# Eliz.net
KiCad netlist of a schematic drawn in EAGLE
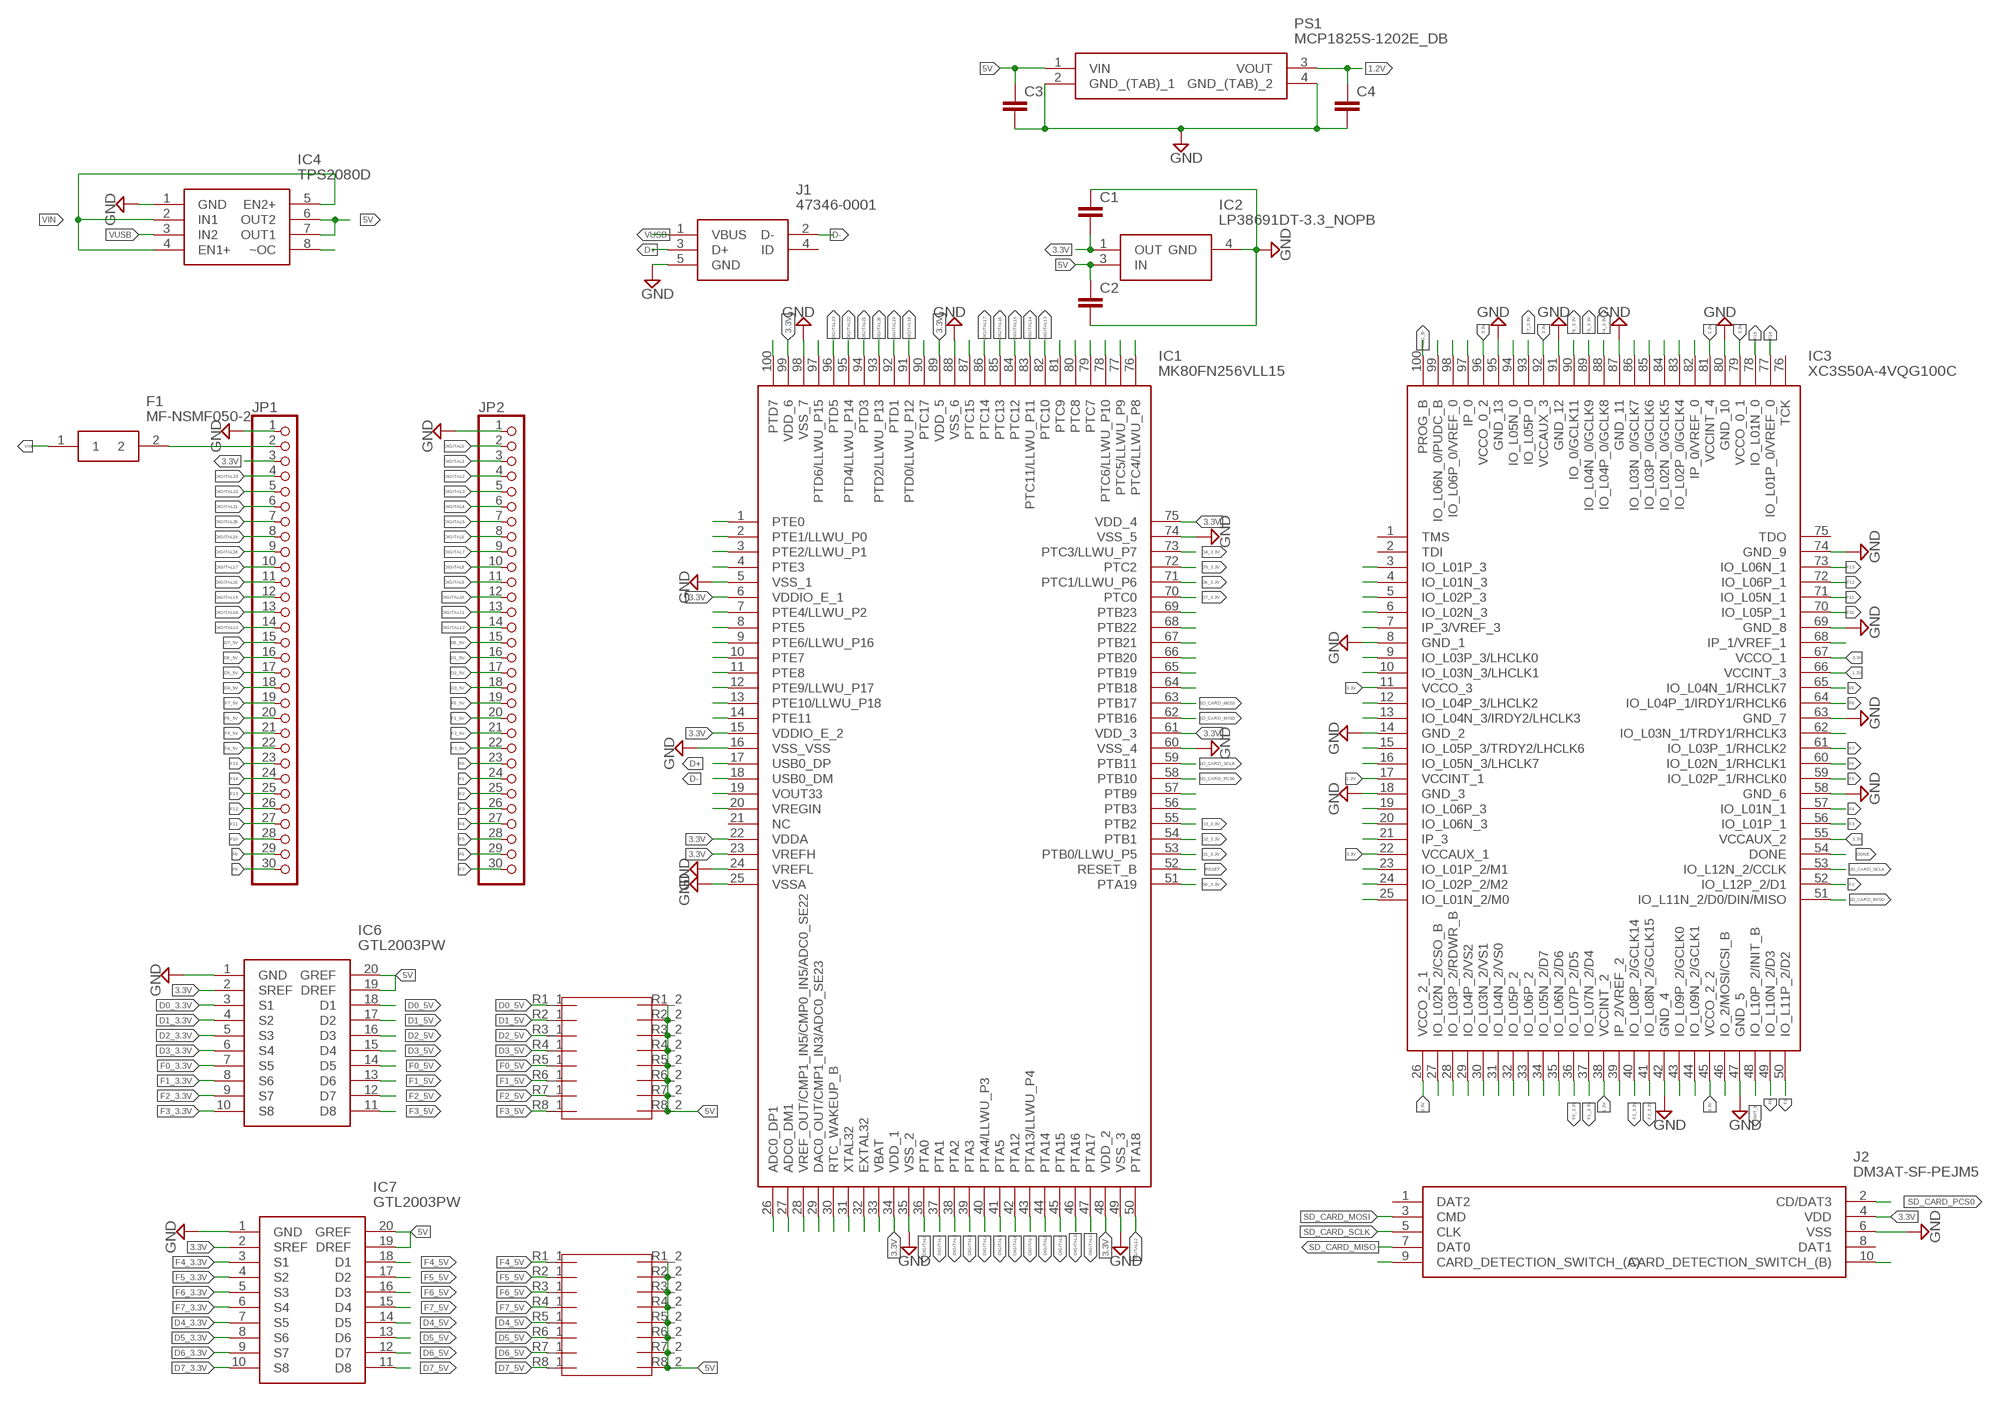
[diagram p0: schematic, sheet 1]

(export (version "E")
  (design (tool "Eeschema 10.0.6"))
  (components
    (comp (ref "C1")
      (value "C-EUC0805")
      (footprint "eagle-import:C0805")
      (libsource (lib "eagle-import") (part "C-EUC0805"))
    )
    (comp (ref "C2")
      (value "C-EUC0805")
      (footprint "eagle-import:C0805")
      (libsource (lib "eagle-import") (part "C-EUC0805"))
    )
    (comp (ref "C3")
      (value "C-EUC0805")
      (footprint "eagle-import:C0805")
      (libsource (lib "eagle-import") (part "C-EUC0805"))
    )
    (comp (ref "C4")
      (value "C-EUC0805")
      (footprint "eagle-import:C0805")
      (libsource (lib "eagle-import") (part "C-EUC0805"))
    )
    (comp (ref "F1")
      (value "MF-NSMF050-2")
      (footprint "eagle-import:FUSC3216X85N")
      (fields (field (name "RS_PART_NUMBER") "6478320P"))
      (libsource (lib "eagle-import") (part "MF-NSMF050-2"))
    )
    (comp (ref "IC1")
      (value "MK80FN256VLL15")
      (footprint "eagle-import:QFP50P1600X1600X170-100N")
      (libsource (lib "eagle-import") (part "MK80FN256VLL15"))
    )
    (comp (ref "IC2")
      (value "LP38691DT-3.3_NOPB")
      (footprint "eagle-import:TO228P991X238-3N")
      (fields
        (field (name "ARROW_PART_NUMBER") "LP38691DT-3.3/NOPB")
        (field (name "RS_PART_NUMBER") "5378730P")
      )
      (libsource (lib "eagle-import") (part "LP38691DT-3.3_NOPB"))
    )
    (comp (ref "IC3")
      (value "XC3S50A-4VQG100C")
      (footprint "eagle-import:QFP50P1600X1600X120-100N")
      (fields (field (name "RS_PART_NUMBER") "1732062"))
      (libsource (lib "eagle-import") (part "XC3S50A-4VQG100C"))
    )
    (comp (ref "IC4")
      (value "TPS2080D")
      (footprint "eagle-import:SOIC127P600X175-8N")
      (fields (field (name "RS_PART_NUMBER") "6608007P"))
      (libsource (lib "eagle-import") (part "TPS2080D"))
    )
    (comp (ref "IC6")
      (value "GTL2003PW")
      (footprint "eagle-import:SOP65P640X110-20N")
      (fields (field (name "RS_PART_NUMBER") "510960"))
      (libsource (lib "eagle-import") (part "GTL2003PW"))
    )
    (comp (ref "IC7")
      (value "GTL2003PW")
      (footprint "eagle-import:SOP65P640X110-20N")
      (fields (field (name "RS_PART_NUMBER") "510960"))
      (libsource (lib "eagle-import") (part "GTL2003PW"))
    )
    (comp (ref "J1")
      (value "47346-0001")
      (footprint "eagle-import:47346-0001")
      (fields (field (name "RS_PART_NUMBER") "7025475P"))
      (libsource (lib "eagle-import") (part "47346-0001"))
    )
    (comp (ref "J2")
      (value "DM3AT-SF-PEJM5")
      (footprint "eagle-import:DM3AT-SF-PEJM5_1")
      (fields (field (name "RS_PART_NUMBER") "1722520"))
      (libsource (lib "eagle-import") (part "DM3AT-SF-PEJM5"))
    )
    (comp (ref "JP1")
      (value "PINHD-1X30")
      (footprint "eagle-import:1X30")
      (libsource (lib "eagle-import") (part "PINHD-1X30"))
    )
    (comp (ref "JP2")
      (value "PINHD-1X30")
      (footprint "eagle-import:1X30")
      (libsource (lib "eagle-import") (part "PINHD-1X30"))
    )
    (comp (ref "PS1")
      (value "MCP1825S-1202E_DB")
      (footprint "eagle-import:SOT230P700X180-4N")
      (fields
        (field (name "ARROW_PART_NUMBER") "MCP1825S-1202E/DB")
        (field (name "RS_PART_NUMBER") "1651983")
      )
      (libsource (lib "eagle-import") (part "MCP1825S-1202E_DB"))
    )
    (comp (ref "U$1")
      (value "EXB2HV472JV")
      (footprint "eagle-import:8_4,7KOHM")
      (fields (field (name "MF") "Panasonic"))
      (libsource (lib "eagle-import") (part "EXB2HV472JV"))
    )
    (comp (ref "U$2")
      (value "EXB2HV472JV")
      (footprint "eagle-import:8_4,7KOHM")
      (fields (field (name "MF") "Panasonic"))
      (libsource (lib "eagle-import") (part "EXB2HV472JV"))
    )
  )
  (nets
    (net (code "1") (name "1.2V") (class "Default")
      (node (ref "C4") (pin "1") (pinfunction "1_1") (pintype "passive"))
      (node (ref "IC3") (pin "17") (pinfunction "VCCINT_1_17") (pintype "bidirectional"))
      (node (ref "IC3") (pin "38") (pinfunction "VCCINT_2_38") (pintype "bidirectional"))
      (node (ref "IC3") (pin "66") (pinfunction "VCCINT_3_66") (pintype "bidirectional"))
      (node (ref "IC3") (pin "81") (pinfunction "VCCINT_4_81") (pintype "bidirectional"))
      (node (ref "PS1") (pin "3") (pinfunction "VOUT_3") (pintype "output"))
    )
    (net (code "2") (name "3.3V") (class "Default")
      (node (ref "C1") (pin "2") (pinfunction "2_2") (pintype "passive"))
      (node (ref "IC1") (pin "15") (pinfunction "VDDIO_E_2_15") (pintype "bidirectional"))
      (node (ref "IC1") (pin "22") (pinfunction "VDDA_22") (pintype "bidirectional"))
      (node (ref "IC1") (pin "23") (pinfunction "VREFH_23") (pintype "bidirectional"))
      (node (ref "IC1") (pin "34") (pinfunction "VDD_1_34") (pintype "bidirectional"))
      (node (ref "IC1") (pin "48") (pinfunction "VDD_2_48") (pintype "bidirectional"))
      (node (ref "IC1") (pin "6") (pinfunction "VDDIO_E_1_6") (pintype "bidirectional"))
      (node (ref "IC1") (pin "61") (pinfunction "VDD_3_61") (pintype "bidirectional"))
      (node (ref "IC1") (pin "75") (pinfunction "VDD_4_75") (pintype "bidirectional"))
      (node (ref "IC1") (pin "89") (pinfunction "VDD_5_89") (pintype "bidirectional"))
      (node (ref "IC1") (pin "99") (pinfunction "VDD_6_99") (pintype "bidirectional"))
      (node (ref "IC2") (pin "1") (pinfunction "OUT_1") (pintype "output"))
      (node (ref "IC3") (pin "11") (pinfunction "VCCO_3_11") (pintype "bidirectional"))
      (node (ref "IC3") (pin "22") (pinfunction "VCCAUX_1_22") (pintype "bidirectional"))
      (node (ref "IC3") (pin "26") (pinfunction "VCCO_2_1_26") (pintype "bidirectional"))
      (node (ref "IC3") (pin "45") (pinfunction "VCCO_2_2_45") (pintype "bidirectional"))
      (node (ref "IC3") (pin "55") (pinfunction "VCCAUX_2_55") (pintype "bidirectional"))
      (node (ref "IC3") (pin "67") (pinfunction "VCCO_1_67") (pintype "bidirectional"))
      (node (ref "IC3") (pin "79") (pinfunction "VCCO_0_1_79") (pintype "bidirectional"))
      (node (ref "IC3") (pin "92") (pinfunction "VCCAUX_3_92") (pintype "bidirectional"))
      (node (ref "IC3") (pin "96") (pinfunction "VCCO_0_2_96") (pintype "bidirectional"))
      (node (ref "IC6") (pin "2") (pinfunction "SREF_2") (pintype "input"))
      (node (ref "IC7") (pin "2") (pinfunction "SREF_2") (pintype "input"))
      (node (ref "J2") (pin "4") (pinfunction "VDD_4") (pintype "bidirectional"))
      (node (ref "JP1") (pin "3") (pinfunction "3_3") (pintype "passive"))
    )
    (net (code "3") (name "5V") (class "Default")
      (node (ref "C2") (pin "1") (pinfunction "1_1") (pintype "passive"))
      (node (ref "C3") (pin "1") (pinfunction "1_1") (pintype "passive"))
      (node (ref "IC2") (pin "3") (pinfunction "IN_3") (pintype "input"))
      (node (ref "IC4") (pin "6") (pinfunction "OUT2_6") (pintype "bidirectional"))
      (node (ref "IC4") (pin "7") (pinfunction "OUT1_7") (pintype "bidirectional"))
      (node (ref "IC6") (pin "19") (pinfunction "DREF_19") (pintype "input"))
      (node (ref "IC6") (pin "20") (pinfunction "GREF_20") (pintype "input"))
      (node (ref "IC7") (pin "19") (pinfunction "DREF_19") (pintype "input"))
      (node (ref "IC7") (pin "20") (pinfunction "GREF_20") (pintype "input"))
      (node (ref "PS1") (pin "1") (pinfunction "VIN_1") (pintype "input"))
      (node (ref "U$1") (pin "R1_2") (pinfunction "R1_2_R1_2") (pintype "bidirectional"))
      (node (ref "U$1") (pin "R2_2") (pinfunction "R2_2_R2_2") (pintype "bidirectional"))
      (node (ref "U$1") (pin "R3_2") (pinfunction "R3_2_R3_2") (pintype "bidirectional"))
      (node (ref "U$1") (pin "R4_2") (pinfunction "R4_2_R4_2") (pintype "bidirectional"))
      (node (ref "U$1") (pin "R5_2") (pinfunction "R5_2_R5_2") (pintype "bidirectional"))
      (node (ref "U$1") (pin "R6_2") (pinfunction "R6_2_R6_2") (pintype "bidirectional"))
      (node (ref "U$1") (pin "R7_2") (pinfunction "R7_2_R7_2") (pintype "bidirectional"))
      (node (ref "U$1") (pin "R8_2") (pinfunction "R8_2_R8_2") (pintype "bidirectional"))
      (node (ref "U$2") (pin "R1_2") (pinfunction "R1_2_R1_2") (pintype "bidirectional"))
      (node (ref "U$2") (pin "R2_2") (pinfunction "R2_2_R2_2") (pintype "bidirectional"))
      (node (ref "U$2") (pin "R3_2") (pinfunction "R3_2_R3_2") (pintype "bidirectional"))
      (node (ref "U$2") (pin "R4_2") (pinfunction "R4_2_R4_2") (pintype "bidirectional"))
      (node (ref "U$2") (pin "R5_2") (pinfunction "R5_2_R5_2") (pintype "bidirectional"))
      (node (ref "U$2") (pin "R6_2") (pinfunction "R6_2_R6_2") (pintype "bidirectional"))
      (node (ref "U$2") (pin "R7_2") (pinfunction "R7_2_R7_2") (pintype "bidirectional"))
      (node (ref "U$2") (pin "R8_2") (pinfunction "R8_2_R8_2") (pintype "bidirectional"))
    )
    (net (code "4") (name "D+") (class "Default")
      (node (ref "IC1") (pin "17") (pinfunction "USB0_DP_17") (pintype "bidirectional"))
      (node (ref "J1") (pin "3") (pinfunction "D+_3") (pintype "bidirectional"))
    )
    (net (code "5") (name "D-") (class "Default")
      (node (ref "IC1") (pin "18") (pinfunction "USB0_DM_18") (pintype "bidirectional"))
      (node (ref "J1") (pin "2") (pinfunction "D-_2") (pintype "bidirectional"))
    )
    (net (code "6") (name "D0_3.3V") (class "Default")
      (node (ref "IC1") (pin "51") (pinfunction "PTA19_51") (pintype "bidirectional"))
      (node (ref "IC6") (pin "3") (pinfunction "S1_3") (pintype "bidirectional"))
    )
    (net (code "7") (name "D0_5V") (class "Default")
      (node (ref "IC6") (pin "18") (pinfunction "D1_18") (pintype "bidirectional"))
      (node (ref "JP2") (pin "15") (pinfunction "15_15") (pintype "passive"))
      (node (ref "U$1") (pin "R1_1") (pinfunction "R1_1_R1_1") (pintype "bidirectional"))
    )
    (net (code "8") (name "D1_3.3V") (class "Default")
      (node (ref "IC1") (pin "53") (pinfunction "PTB0/LLWU_P5_53") (pintype "bidirectional"))
      (node (ref "IC6") (pin "4") (pinfunction "S2_4") (pintype "bidirectional"))
    )
    (net (code "9") (name "D1_5V") (class "Default")
      (node (ref "IC6") (pin "17") (pinfunction "D2_17") (pintype "bidirectional"))
      (node (ref "JP2") (pin "16") (pinfunction "16_16") (pintype "passive"))
      (node (ref "U$1") (pin "R2_1") (pinfunction "R2_1_R2_1") (pintype "bidirectional"))
    )
    (net (code "10") (name "D2_3.3V") (class "Default")
      (node (ref "IC1") (pin "54") (pinfunction "PTB1_54") (pintype "bidirectional"))
      (node (ref "IC6") (pin "5") (pinfunction "S3_5") (pintype "bidirectional"))
    )
    (net (code "11") (name "D2_5V") (class "Default")
      (node (ref "IC6") (pin "16") (pinfunction "D3_16") (pintype "bidirectional"))
      (node (ref "JP2") (pin "17") (pinfunction "17_17") (pintype "passive"))
      (node (ref "U$1") (pin "R3_1") (pinfunction "R3_1_R3_1") (pintype "bidirectional"))
    )
    (net (code "12") (name "D3_3.3V") (class "Default")
      (node (ref "IC1") (pin "55") (pinfunction "PTB2_55") (pintype "bidirectional"))
      (node (ref "IC6") (pin "6") (pinfunction "S4_6") (pintype "bidirectional"))
    )
    (net (code "13") (name "D3_5V") (class "Default")
      (node (ref "IC6") (pin "15") (pinfunction "D4_15") (pintype "bidirectional"))
      (node (ref "JP2") (pin "18") (pinfunction "18_18") (pintype "passive"))
      (node (ref "U$1") (pin "R4_1") (pinfunction "R4_1_R4_1") (pintype "bidirectional"))
    )
    (net (code "14") (name "D4_3.3V") (class "Default")
      (node (ref "IC1") (pin "73") (pinfunction "PTC3/LLWU_P7_73") (pintype "bidirectional"))
      (node (ref "IC7") (pin "7") (pinfunction "S5_7") (pintype "bidirectional"))
    )
    (net (code "15") (name "D4_5V") (class "Default")
      (node (ref "IC7") (pin "14") (pinfunction "D5_14") (pintype "bidirectional"))
      (node (ref "JP1") (pin "18") (pinfunction "18_18") (pintype "passive"))
      (node (ref "U$2") (pin "R5_1") (pinfunction "R5_1_R5_1") (pintype "bidirectional"))
    )
    (net (code "16") (name "D5_3.3V") (class "Default")
      (node (ref "IC1") (pin "72") (pinfunction "PTC2_72") (pintype "bidirectional"))
      (node (ref "IC7") (pin "8") (pinfunction "S6_8") (pintype "bidirectional"))
    )
    (net (code "17") (name "D5_5V") (class "Default")
      (node (ref "IC7") (pin "13") (pinfunction "D6_13") (pintype "bidirectional"))
      (node (ref "JP1") (pin "17") (pinfunction "17_17") (pintype "passive"))
      (node (ref "U$2") (pin "R6_1") (pinfunction "R6_1_R6_1") (pintype "bidirectional"))
    )
    (net (code "18") (name "D6_3.3V") (class "Default")
      (node (ref "IC1") (pin "71") (pinfunction "PTC1/LLWU_P6_71") (pintype "bidirectional"))
      (node (ref "IC7") (pin "9") (pinfunction "S7_9") (pintype "bidirectional"))
    )
    (net (code "19") (name "D6_5V") (class "Default")
      (node (ref "IC7") (pin "12") (pinfunction "D7_12") (pintype "bidirectional"))
      (node (ref "JP1") (pin "16") (pinfunction "16_16") (pintype "passive"))
      (node (ref "U$2") (pin "R7_1") (pinfunction "R7_1_R7_1") (pintype "bidirectional"))
    )
    (net (code "20") (name "D7_3.3V") (class "Default")
      (node (ref "IC1") (pin "70") (pinfunction "PTC0_70") (pintype "bidirectional"))
      (node (ref "IC7") (pin "10") (pinfunction "S8_10") (pintype "bidirectional"))
    )
    (net (code "21") (name "D7_5V") (class "Default")
      (node (ref "IC7") (pin "11") (pinfunction "D8_11") (pintype "bidirectional"))
      (node (ref "JP1") (pin "15") (pinfunction "15_15") (pintype "passive"))
      (node (ref "U$2") (pin "R8_1") (pinfunction "R8_1_R8_1") (pintype "bidirectional"))
    )
    (net (code "22") (name "DIGITAL0") (class "Default")
      (node (ref "IC1") (pin "36") (pinfunction "PTA0_36") (pintype "bidirectional"))
      (node (ref "JP2") (pin "2") (pinfunction "2_2") (pintype "passive"))
    )
    (net (code "23") (name "DIGITAL1") (class "Default")
      (node (ref "IC1") (pin "37") (pinfunction "PTA1_37") (pintype "bidirectional"))
      (node (ref "JP2") (pin "3") (pinfunction "3_3") (pintype "passive"))
    )
    (net (code "24") (name "DIGITAL2") (class "Default")
      (node (ref "IC1") (pin "38") (pinfunction "PTA2_38") (pintype "bidirectional"))
      (node (ref "JP2") (pin "4") (pinfunction "4_4") (pintype "passive"))
    )
    (net (code "25") (name "DIGITAL3") (class "Default")
      (node (ref "IC1") (pin "39") (pinfunction "PTA3_39") (pintype "bidirectional"))
      (node (ref "JP2") (pin "5") (pinfunction "5_5") (pintype "passive"))
    )
    (net (code "26") (name "DIGITAL4") (class "Default")
      (node (ref "IC1") (pin "40") (pinfunction "PTA4/LLWU_P3_40") (pintype "bidirectional"))
      (node (ref "JP2") (pin "6") (pinfunction "6_6") (pintype "passive"))
    )
    (net (code "27") (name "DIGITAL5") (class "Default")
      (node (ref "IC1") (pin "41") (pinfunction "PTA5_41") (pintype "bidirectional"))
      (node (ref "JP2") (pin "7") (pinfunction "7_7") (pintype "passive"))
    )
    (net (code "28") (name "DIGITAL6") (class "Default")
      (node (ref "IC1") (pin "42") (pinfunction "PTA12_42") (pintype "bidirectional"))
      (node (ref "JP2") (pin "8") (pinfunction "8_8") (pintype "passive"))
    )
    (net (code "29") (name "DIGITAL7") (class "Default")
      (node (ref "IC1") (pin "43") (pinfunction "PTA13/LLWU_P4_43") (pintype "bidirectional"))
      (node (ref "JP2") (pin "9") (pinfunction "9_9") (pintype "passive"))
    )
    (net (code "30") (name "DIGITAL8") (class "Default")
      (node (ref "IC1") (pin "44") (pinfunction "PTA14_44") (pintype "bidirectional"))
      (node (ref "JP2") (pin "10") (pinfunction "10_10") (pintype "passive"))
    )
    (net (code "31") (name "DIGITAL9") (class "Default")
      (node (ref "IC1") (pin "45") (pinfunction "PTA15_45") (pintype "bidirectional"))
      (node (ref "JP2") (pin "11") (pinfunction "11_11") (pintype "passive"))
    )
    (net (code "32") (name "DIGITAL10") (class "Default")
      (node (ref "IC1") (pin "46") (pinfunction "PTA16_46") (pintype "bidirectional"))
      (node (ref "JP2") (pin "12") (pinfunction "12_12") (pintype "passive"))
    )
    (net (code "33") (name "DIGITAL11") (class "Default")
      (node (ref "IC1") (pin "47") (pinfunction "PTA17_47") (pintype "bidirectional"))
      (node (ref "JP2") (pin "13") (pinfunction "13_13") (pintype "passive"))
    )
    (net (code "34") (name "DIGITAL12") (class "Default")
      (node (ref "IC1") (pin "50") (pinfunction "PTA18_50") (pintype "bidirectional"))
      (node (ref "JP2") (pin "14") (pinfunction "14_14") (pintype "passive"))
    )
    (net (code "35") (name "DIGITAL13") (class "Default")
      (node (ref "IC1") (pin "82") (pinfunction "PTC10_82") (pintype "bidirectional"))
      (node (ref "JP1") (pin "14") (pinfunction "14_14") (pintype "passive"))
    )
    (net (code "36") (name "DIGITAL14") (class "Default")
      (node (ref "IC1") (pin "83") (pinfunction "PTC11/LLWU_P11_83") (pintype "bidirectional"))
      (node (ref "JP1") (pin "13") (pinfunction "13_13") (pintype "passive"))
    )
    (net (code "37") (name "DIGITAL15") (class "Default")
      (node (ref "IC1") (pin "84") (pinfunction "PTC12_84") (pintype "bidirectional"))
      (node (ref "JP1") (pin "12") (pinfunction "12_12") (pintype "passive"))
    )
    (net (code "38") (name "DIGITAL16") (class "Default")
      (node (ref "IC1") (pin "85") (pinfunction "PTC13_85") (pintype "bidirectional"))
      (node (ref "JP1") (pin "11") (pinfunction "11_11") (pintype "passive"))
    )
    (net (code "39") (name "DIGITAL17") (class "Default")
      (node (ref "IC1") (pin "86") (pinfunction "PTC14_86") (pintype "bidirectional"))
      (node (ref "JP1") (pin "10") (pinfunction "10_10") (pintype "passive"))
    )
    (net (code "40") (name "DIGITAL18") (class "Default")
      (node (ref "IC1") (pin "91") (pinfunction "PTD0/LLWU_P12_91") (pintype "bidirectional"))
      (node (ref "JP1") (pin "9") (pinfunction "9_9") (pintype "passive"))
    )
    (net (code "41") (name "DIGITAL19") (class "Default")
      (node (ref "IC1") (pin "92") (pinfunction "PTD1_92") (pintype "bidirectional"))
      (node (ref "JP1") (pin "8") (pinfunction "8_8") (pintype "passive"))
    )
    (net (code "42") (name "DIGITAL20") (class "Default")
      (node (ref "IC1") (pin "93") (pinfunction "PTD2/LLWU_P13_93") (pintype "bidirectional"))
      (node (ref "JP1") (pin "7") (pinfunction "7_7") (pintype "passive"))
    )
    (net (code "43") (name "DIGITAL21") (class "Default")
      (node (ref "IC1") (pin "94") (pinfunction "PTD3_94") (pintype "bidirectional"))
      (node (ref "JP1") (pin "6") (pinfunction "6_6") (pintype "passive"))
    )
    (net (code "44") (name "DIGITAL22") (class "Default")
      (node (ref "IC1") (pin "95") (pinfunction "PTD4/LLWU_P14_95") (pintype "bidirectional"))
      (node (ref "JP1") (pin "5") (pinfunction "5_5") (pintype "passive"))
    )
    (net (code "45") (name "DIGITAL23") (class "Default")
      (node (ref "IC1") (pin "96") (pinfunction "PTD5_96") (pintype "bidirectional"))
      (node (ref "JP1") (pin "4") (pinfunction "4_4") (pintype "passive"))
    )
    (net (code "46") (name "DONE") (class "Default")
      (node (ref "IC3") (pin "54") (pinfunction "DONE_54") (pintype "bidirectional"))
    )
    (net (code "47") (name "F0") (class "Default")
      (node (ref "IC3") (pin "49") (pinfunction "IO_L10N_2/D3_49") (pintype "bidirectional"))
      (node (ref "JP2") (pin "23") (pinfunction "23_23") (pintype "passive"))
    )
    (net (code "48") (name "F0_3.3V") (class "Default")
      (node (ref "IC3") (pin "36") (pinfunction "IO_L07P_2/D5_36") (pintype "bidirectional"))
      (node (ref "IC6") (pin "7") (pinfunction "S5_7") (pintype "bidirectional"))
    )
    (net (code "49") (name "F0_5V") (class "Default")
      (node (ref "IC6") (pin "14") (pinfunction "D5_14") (pintype "bidirectional"))
      (node (ref "JP2") (pin "19") (pinfunction "19_19") (pintype "passive"))
      (node (ref "U$1") (pin "R5_1") (pinfunction "R5_1_R5_1") (pintype "bidirectional"))
    )
    (net (code "50") (name "F1") (class "Default")
      (node (ref "IC3") (pin "50") (pinfunction "IO_L11P_2/D2_50") (pintype "bidirectional"))
      (node (ref "JP2") (pin "24") (pinfunction "24_24") (pintype "passive"))
    )
    (net (code "51") (name "F1_3.3V") (class "Default")
      (node (ref "IC3") (pin "37") (pinfunction "IO_L07N_2/D4_37") (pintype "bidirectional"))
      (node (ref "IC6") (pin "8") (pinfunction "S6_8") (pintype "bidirectional"))
    )
    (net (code "52") (name "F1_5V") (class "Default")
      (node (ref "IC6") (pin "13") (pinfunction "D6_13") (pintype "bidirectional"))
      (node (ref "JP2") (pin "20") (pinfunction "20_20") (pintype "passive"))
      (node (ref "U$1") (pin "R6_1") (pinfunction "R6_1_R6_1") (pintype "bidirectional"))
    )
    (net (code "53") (name "F2") (class "Default")
      (node (ref "IC3") (pin "52") (pinfunction "IO_L12P_2/D1_52") (pintype "bidirectional"))
      (node (ref "JP2") (pin "25") (pinfunction "25_25") (pintype "passive"))
    )
    (net (code "54") (name "F2_3.3V") (class "Default")
      (node (ref "IC3") (pin "40") (pinfunction "IO_L08P_2/GCLK14_40") (pintype "bidirectional"))
      (node (ref "IC6") (pin "9") (pinfunction "S7_9") (pintype "bidirectional"))
    )
    (net (code "55") (name "F2_5V") (class "Default")
      (node (ref "IC6") (pin "12") (pinfunction "D7_12") (pintype "bidirectional"))
      (node (ref "JP2") (pin "21") (pinfunction "21_21") (pintype "passive"))
      (node (ref "U$1") (pin "R7_1") (pinfunction "R7_1_R7_1") (pintype "bidirectional"))
    )
    (net (code "56") (name "F3") (class "Default")
      (node (ref "IC3") (pin "56") (pinfunction "IO_L01P_1_56") (pintype "bidirectional"))
      (node (ref "JP2") (pin "26") (pinfunction "26_26") (pintype "passive"))
    )
    (net (code "57") (name "F3_3.3V") (class "Default")
      (node (ref "IC3") (pin "41") (pinfunction "IO_L08N_2/GCLK15_41") (pintype "bidirectional"))
      (node (ref "IC6") (pin "10") (pinfunction "S8_10") (pintype "bidirectional"))
    )
    (net (code "58") (name "F3_5V") (class "Default")
      (node (ref "IC6") (pin "11") (pinfunction "D8_11") (pintype "bidirectional"))
      (node (ref "JP2") (pin "22") (pinfunction "22_22") (pintype "passive"))
      (node (ref "U$1") (pin "R8_1") (pinfunction "R8_1_R8_1") (pintype "bidirectional"))
    )
    (net (code "59") (name "F4") (class "Default")
      (node (ref "IC3") (pin "57") (pinfunction "IO_L01N_1_57") (pintype "bidirectional"))
      (node (ref "JP2") (pin "27") (pinfunction "27_27") (pintype "passive"))
    )
    (net (code "60") (name "F4_3.3V") (class "Default")
      (node (ref "IC3") (pin "88") (pinfunction "IO_L04P_0/GCLK8_88") (pintype "bidirectional"))
      (node (ref "IC7") (pin "3") (pinfunction "S1_3") (pintype "bidirectional"))
    )
    (net (code "61") (name "F4_5V") (class "Default")
      (node (ref "IC7") (pin "18") (pinfunction "D1_18") (pintype "bidirectional"))
      (node (ref "JP1") (pin "22") (pinfunction "22_22") (pintype "passive"))
      (node (ref "U$2") (pin "R1_1") (pinfunction "R1_1_R1_1") (pintype "bidirectional"))
    )
    (net (code "62") (name "F5") (class "Default")
      (node (ref "IC3") (pin "59") (pinfunction "IO_L02P_1/RHCLK0_59") (pintype "bidirectional"))
      (node (ref "JP2") (pin "28") (pinfunction "28_28") (pintype "passive"))
    )
    (net (code "63") (name "F5_3.3V") (class "Default")
      (node (ref "IC3") (pin "89") (pinfunction "IO_L04N_0/GCLK9_89") (pintype "bidirectional"))
      (node (ref "IC7") (pin "4") (pinfunction "S2_4") (pintype "bidirectional"))
    )
    (net (code "64") (name "F5_5V") (class "Default")
      (node (ref "IC7") (pin "17") (pinfunction "D2_17") (pintype "bidirectional"))
      (node (ref "JP1") (pin "21") (pinfunction "21_21") (pintype "passive"))
      (node (ref "U$2") (pin "R2_1") (pinfunction "R2_1_R2_1") (pintype "bidirectional"))
    )
    (net (code "65") (name "F6") (class "Default")
      (node (ref "IC3") (pin "60") (pinfunction "IO_L02N_1/RHCLK1_60") (pintype "bidirectional"))
      (node (ref "JP2") (pin "29") (pinfunction "29_29") (pintype "passive"))
    )
    (net (code "66") (name "F6_3.3V") (class "Default")
      (node (ref "IC3") (pin "90") (pinfunction "IO_0/GCLK11_90") (pintype "bidirectional"))
      (node (ref "IC7") (pin "5") (pinfunction "S3_5") (pintype "bidirectional"))
    )
    (net (code "67") (name "F6_5V") (class "Default")
      (node (ref "IC7") (pin "16") (pinfunction "D3_16") (pintype "bidirectional"))
      (node (ref "JP1") (pin "20") (pinfunction "20_20") (pintype "passive"))
      (node (ref "U$2") (pin "R3_1") (pinfunction "R3_1_R3_1") (pintype "bidirectional"))
    )
    (net (code "68") (name "F7") (class "Default")
      (node (ref "IC3") (pin "61") (pinfunction "IO_L03P_1/RHCLK2_61") (pintype "bidirectional"))
      (node (ref "JP2") (pin "30") (pinfunction "30_30") (pintype "passive"))
    )
    (net (code "69") (name "F7_3.3V") (class "Default")
      (node (ref "IC3") (pin "93") (pinfunction "IO_L05P_0_93") (pintype "bidirectional"))
      (node (ref "IC7") (pin "6") (pinfunction "S4_6") (pintype "bidirectional"))
    )
    (net (code "70") (name "F7_5V") (class "Default")
      (node (ref "IC7") (pin "15") (pinfunction "D4_15") (pintype "bidirectional"))
      (node (ref "JP1") (pin "19") (pinfunction "19_19") (pintype "passive"))
      (node (ref "U$2") (pin "R4_1") (pinfunction "R4_1_R4_1") (pintype "bidirectional"))
    )
    (net (code "71") (name "F8") (class "Default")
      (node (ref "IC3") (pin "64") (pinfunction "IO_L04P_1/IRDY1/RHCLK6_64") (pintype "bidirectional"))
      (node (ref "JP1") (pin "30") (pinfunction "30_30") (pintype "passive"))
    )
    (net (code "72") (name "F9") (class "Default")
      (node (ref "IC3") (pin "65") (pinfunction "IO_L04N_1/RHCLK7_65") (pintype "bidirectional"))
      (node (ref "JP1") (pin "29") (pinfunction "29_29") (pintype "passive"))
    )
    (net (code "73") (name "F10") (class "Default")
      (node (ref "IC3") (pin "70") (pinfunction "IO_L05P_1_70") (pintype "bidirectional"))
      (node (ref "JP1") (pin "28") (pinfunction "28_28") (pintype "passive"))
    )
    (net (code "74") (name "F11") (class "Default")
      (node (ref "IC3") (pin "71") (pinfunction "IO_L05N_1_71") (pintype "bidirectional"))
      (node (ref "JP1") (pin "27") (pinfunction "27_27") (pintype "passive"))
    )
    (net (code "75") (name "F12") (class "Default")
      (node (ref "IC3") (pin "72") (pinfunction "IO_L06P_1_72") (pintype "bidirectional"))
      (node (ref "JP1") (pin "26") (pinfunction "26_26") (pintype "passive"))
    )
    (net (code "76") (name "F13") (class "Default")
      (node (ref "IC3") (pin "73") (pinfunction "IO_L06N_1_73") (pintype "bidirectional"))
      (node (ref "JP1") (pin "25") (pinfunction "25_25") (pintype "passive"))
    )
    (net (code "77") (name "F14") (class "Default")
      (node (ref "IC3") (pin "77") (pinfunction "IO_L01P_0/VREF_0_77") (pintype "bidirectional"))
      (node (ref "JP1") (pin "24") (pinfunction "24_24") (pintype "passive"))
    )
    (net (code "78") (name "F15") (class "Default")
      (node (ref "IC3") (pin "78") (pinfunction "IO_L01N_0_78") (pintype "bidirectional"))
      (node (ref "JP1") (pin "23") (pinfunction "23_23") (pintype "passive"))
    )
    (net (code "79") (name "GND") (class "Default")
      (node (ref "C1") (pin "1") (pinfunction "1_1") (pintype "passive"))
      (node (ref "C2") (pin "2") (pinfunction "2_2") (pintype "passive"))
      (node (ref "C3") (pin "2") (pinfunction "2_2") (pintype "passive"))
      (node (ref "C4") (pin "2") (pinfunction "2_2") (pintype "passive"))
      (node (ref "IC1") (pin "16") (pinfunction "VSS_VSS_16") (pintype "bidirectional"))
      (node (ref "IC1") (pin "24") (pinfunction "VREFL_24") (pintype "bidirectional"))
      (node (ref "IC1") (pin "25") (pinfunction "VSSA_25") (pintype "bidirectional"))
      (node (ref "IC1") (pin "35") (pinfunction "VSS_2_35") (pintype "bidirectional"))
      (node (ref "IC1") (pin "49") (pinfunction "VSS_3_49") (pintype "bidirectional"))
      (node (ref "IC1") (pin "5") (pinfunction "VSS_1_5") (pintype "bidirectional"))
      (node (ref "IC1") (pin "60") (pinfunction "VSS_4_60") (pintype "bidirectional"))
      (node (ref "IC1") (pin "74") (pinfunction "VSS_5_74") (pintype "bidirectional"))
      (node (ref "IC1") (pin "88") (pinfunction "VSS_6_88") (pintype "bidirectional"))
      (node (ref "IC1") (pin "98") (pinfunction "VSS_7_98") (pintype "bidirectional"))
      (node (ref "IC2") (pin "4") (pinfunction "GND_4") (pintype "power_in"))
      (node (ref "IC3") (pin "14") (pinfunction "GND_2_14") (pintype "bidirectional"))
      (node (ref "IC3") (pin "18") (pinfunction "GND_3_18") (pintype "bidirectional"))
      (node (ref "IC3") (pin "42") (pinfunction "GND_4_42") (pintype "bidirectional"))
      (node (ref "IC3") (pin "47") (pinfunction "GND_5_47") (pintype "bidirectional"))
      (node (ref "IC3") (pin "58") (pinfunction "GND_6_58") (pintype "bidirectional"))
      (node (ref "IC3") (pin "63") (pinfunction "GND_7_63") (pintype "bidirectional"))
      (node (ref "IC3") (pin "69") (pinfunction "GND_8_69") (pintype "bidirectional"))
      (node (ref "IC3") (pin "74") (pinfunction "GND_9_74") (pintype "bidirectional"))
      (node (ref "IC3") (pin "8") (pinfunction "GND_1_8") (pintype "bidirectional"))
      (node (ref "IC3") (pin "80") (pinfunction "GND_10_80") (pintype "bidirectional"))
      (node (ref "IC3") (pin "87") (pinfunction "GND_11_87") (pintype "bidirectional"))
      (node (ref "IC3") (pin "91") (pinfunction "GND_12_91") (pintype "bidirectional"))
      (node (ref "IC3") (pin "95") (pinfunction "GND_13_95") (pintype "bidirectional"))
      (node (ref "IC4") (pin "1") (pinfunction "GND_1") (pintype "bidirectional"))
      (node (ref "IC6") (pin "1") (pinfunction "GND_1") (pintype "power_in"))
      (node (ref "IC7") (pin "1") (pinfunction "GND_1") (pintype "power_in"))
      (node (ref "J1") (pin "5") (pinfunction "GND_5") (pintype "bidirectional"))
      (node (ref "J2") (pin "6") (pinfunction "VSS_6") (pintype "bidirectional"))
      (node (ref "JP1") (pin "1") (pinfunction "1_1") (pintype "passive"))
      (node (ref "JP2") (pin "1") (pinfunction "1_1") (pintype "passive"))
      (node (ref "PS1") (pin "2") (pinfunction "GND_(TAB)_1_2") (pintype "power_in"))
      (node (ref "PS1") (pin "4") (pinfunction "GND_(TAB)_2_4") (pintype "power_in"))
    )
    (net (code "80") (name "INIT_B") (class "Default")
      (node (ref "IC3") (pin "48") (pinfunction "IO_L10P_2/INIT_B_48") (pintype "bidirectional"))
    )
    (net (code "81") (name "Net-(F1-Pad2)") (class "Default")
      (node (ref "F1") (pin "2") (pinfunction "2_2") (pintype "bidirectional"))
      (node (ref "JP1") (pin "2") (pinfunction "2_2") (pintype "passive"))
    )
    (net (code "82") (name "PROG_B") (class "Default")
      (node (ref "IC3") (pin "100") (pinfunction "PROG_B_100") (pintype "bidirectional"))
    )
    (net (code "83") (name "RESET") (class "Default")
      (node (ref "IC1") (pin "52") (pinfunction "RESET_B_52") (pintype "bidirectional"))
    )
    (net (code "84") (name "SD_CARD_MISO") (class "Default")
      (node (ref "IC1") (pin "62") (pinfunction "PTB16_62") (pintype "bidirectional"))
      (node (ref "IC3") (pin "51") (pinfunction "IO_L11N_2/D0/DIN/MISO_51") (pintype "bidirectional"))
      (node (ref "J2") (pin "7") (pinfunction "DAT0_7") (pintype "bidirectional"))
    )
    (net (code "85") (name "SD_CARD_MOSI") (class "Default")
      (node (ref "IC1") (pin "63") (pinfunction "PTB17_63") (pintype "bidirectional"))
      (node (ref "J2") (pin "3") (pinfunction "CMD_3") (pintype "bidirectional"))
    )
    (net (code "86") (name "SD_CARD_PCS0") (class "Default")
      (node (ref "IC1") (pin "58") (pinfunction "PTB10_58") (pintype "bidirectional"))
      (node (ref "J2") (pin "2") (pinfunction "CD/DAT3_2") (pintype "bidirectional"))
    )
    (net (code "87") (name "SD_CARD_SCLK") (class "Default")
      (node (ref "IC1") (pin "59") (pinfunction "PTB11_59") (pintype "bidirectional"))
      (node (ref "IC3") (pin "53") (pinfunction "IO_L12N_2/CCLK_53") (pintype "bidirectional"))
      (node (ref "J2") (pin "5") (pinfunction "CLK_5") (pintype "bidirectional"))
    )
    (net (code "88") (name "VIN") (class "Default")
      (node (ref "F1") (pin "1") (pinfunction "1_1") (pintype "bidirectional"))
      (node (ref "IC4") (pin "2") (pinfunction "IN1_2") (pintype "bidirectional"))
      (node (ref "IC4") (pin "4") (pinfunction "EN1+_4") (pintype "bidirectional"))
      (node (ref "IC4") (pin "5") (pinfunction "EN2+_5") (pintype "bidirectional"))
    )
    (net (code "89") (name "VUSB") (class "Default")
      (node (ref "IC4") (pin "3") (pinfunction "IN2_3") (pintype "bidirectional"))
      (node (ref "J1") (pin "1") (pinfunction "VBUS_1") (pintype "bidirectional"))
    )
    (net (code "90") (name "unconnected-(IC1-ADC0_DM1-Pad27)") (class "Default")
      (node (ref "IC1") (pin "27") (pinfunction "ADC0_DM1_27") (pintype "bidirectional"))
    )
    (net (code "91") (name "unconnected-(IC1-ADC0_DP1-Pad26)") (class "Default")
      (node (ref "IC1") (pin "26") (pinfunction "ADC0_DP1_26") (pintype "bidirectional"))
    )
    (net (code "92") (name "unconnected-(IC1-DAC0_OUT{slash}CMP1_IN3{slash}ADC0_SE23-Pad29)") (class "Default")
      (node (ref "IC1") (pin "29") (pinfunction "DAC0_OUT/CMP1_IN3/ADC0_SE23_29") (pintype "bidirectional"))
    )
    (net (code "93") (name "unconnected-(IC1-EXTAL32-Pad32)") (class "Default")
      (node (ref "IC1") (pin "32") (pinfunction "EXTAL32_32") (pintype "bidirectional"))
    )
    (net (code "94") (name "unconnected-(IC1-NC-Pad21)") (class "Default")
      (node (ref "IC1") (pin "21") (pinfunction "NC_21") (pintype "no_connect"))
    )
    (net (code "95") (name "unconnected-(IC1-PTB3-Pad56)") (class "Default")
      (node (ref "IC1") (pin "56") (pinfunction "PTB3_56") (pintype "bidirectional"))
    )
    (net (code "96") (name "unconnected-(IC1-PTB9-Pad57)") (class "Default")
      (node (ref "IC1") (pin "57") (pinfunction "PTB9_57") (pintype "bidirectional"))
    )
    (net (code "97") (name "unconnected-(IC1-PTB18-Pad64)") (class "Default")
      (node (ref "IC1") (pin "64") (pinfunction "PTB18_64") (pintype "bidirectional"))
    )
    (net (code "98") (name "unconnected-(IC1-PTB19-Pad65)") (class "Default")
      (node (ref "IC1") (pin "65") (pinfunction "PTB19_65") (pintype "bidirectional"))
    )
    (net (code "99") (name "unconnected-(IC1-PTB20-Pad66)") (class "Default")
      (node (ref "IC1") (pin "66") (pinfunction "PTB20_66") (pintype "bidirectional"))
    )
    (net (code "100") (name "unconnected-(IC1-PTB21-Pad67)") (class "Default")
      (node (ref "IC1") (pin "67") (pinfunction "PTB21_67") (pintype "bidirectional"))
    )
    (net (code "101") (name "unconnected-(IC1-PTB22-Pad68)") (class "Default")
      (node (ref "IC1") (pin "68") (pinfunction "PTB22_68") (pintype "bidirectional"))
    )
    (net (code "102") (name "unconnected-(IC1-PTB23-Pad69)") (class "Default")
      (node (ref "IC1") (pin "69") (pinfunction "PTB23_69") (pintype "bidirectional"))
    )
    (net (code "103") (name "unconnected-(IC1-PTC4{slash}LLWU_P8-Pad76)") (class "Default")
      (node (ref "IC1") (pin "76") (pinfunction "PTC4/LLWU_P8_76") (pintype "bidirectional"))
    )
    (net (code "104") (name "unconnected-(IC1-PTC5{slash}LLWU_P9-Pad77)") (class "Default")
      (node (ref "IC1") (pin "77") (pinfunction "PTC5/LLWU_P9_77") (pintype "bidirectional"))
    )
    (net (code "105") (name "unconnected-(IC1-PTC6{slash}LLWU_P10-Pad78)") (class "Default")
      (node (ref "IC1") (pin "78") (pinfunction "PTC6/LLWU_P10_78") (pintype "bidirectional"))
    )
    (net (code "106") (name "unconnected-(IC1-PTC7-Pad79)") (class "Default")
      (node (ref "IC1") (pin "79") (pinfunction "PTC7_79") (pintype "bidirectional"))
    )
    (net (code "107") (name "unconnected-(IC1-PTC8-Pad80)") (class "Default")
      (node (ref "IC1") (pin "80") (pinfunction "PTC8_80") (pintype "bidirectional"))
    )
    (net (code "108") (name "unconnected-(IC1-PTC9-Pad81)") (class "Default")
      (node (ref "IC1") (pin "81") (pinfunction "PTC9_81") (pintype "bidirectional"))
    )
    (net (code "109") (name "unconnected-(IC1-PTC15-Pad87)") (class "Default")
      (node (ref "IC1") (pin "87") (pinfunction "PTC15_87") (pintype "bidirectional"))
    )
    (net (code "110") (name "unconnected-(IC1-PTC17-Pad90)") (class "Default")
      (node (ref "IC1") (pin "90") (pinfunction "PTC17_90") (pintype "bidirectional"))
    )
    (net (code "111") (name "unconnected-(IC1-PTD6{slash}LLWU_P15-Pad97)") (class "Default")
      (node (ref "IC1") (pin "97") (pinfunction "PTD6/LLWU_P15_97") (pintype "bidirectional"))
    )
    (net (code "112") (name "unconnected-(IC1-PTD7-Pad100)") (class "Default")
      (node (ref "IC1") (pin "100") (pinfunction "PTD7_100") (pintype "bidirectional"))
    )
    (net (code "113") (name "unconnected-(IC1-PTE0-Pad1)") (class "Default")
      (node (ref "IC1") (pin "1") (pinfunction "PTE0_1") (pintype "bidirectional"))
    )
    (net (code "114") (name "unconnected-(IC1-PTE1{slash}LLWU_P0-Pad2)") (class "Default")
      (node (ref "IC1") (pin "2") (pinfunction "PTE1/LLWU_P0_2") (pintype "bidirectional"))
    )
    (net (code "115") (name "unconnected-(IC1-PTE2{slash}LLWU_P1-Pad3)") (class "Default")
      (node (ref "IC1") (pin "3") (pinfunction "PTE2/LLWU_P1_3") (pintype "bidirectional"))
    )
    (net (code "116") (name "unconnected-(IC1-PTE3-Pad4)") (class "Default")
      (node (ref "IC1") (pin "4") (pinfunction "PTE3_4") (pintype "bidirectional"))
    )
    (net (code "117") (name "unconnected-(IC1-PTE4{slash}LLWU_P2-Pad7)") (class "Default")
      (node (ref "IC1") (pin "7") (pinfunction "PTE4/LLWU_P2_7") (pintype "bidirectional"))
    )
    (net (code "118") (name "unconnected-(IC1-PTE5-Pad8)") (class "Default")
      (node (ref "IC1") (pin "8") (pinfunction "PTE5_8") (pintype "bidirectional"))
    )
    (net (code "119") (name "unconnected-(IC1-PTE6{slash}LLWU_P16-Pad9)") (class "Default")
      (node (ref "IC1") (pin "9") (pinfunction "PTE6/LLWU_P16_9") (pintype "bidirectional"))
    )
    (net (code "120") (name "unconnected-(IC1-PTE7-Pad10)") (class "Default")
      (node (ref "IC1") (pin "10") (pinfunction "PTE7_10") (pintype "bidirectional"))
    )
    (net (code "121") (name "unconnected-(IC1-PTE8-Pad11)") (class "Default")
      (node (ref "IC1") (pin "11") (pinfunction "PTE8_11") (pintype "bidirectional"))
    )
    (net (code "122") (name "unconnected-(IC1-PTE9{slash}LLWU_P17-Pad12)") (class "Default")
      (node (ref "IC1") (pin "12") (pinfunction "PTE9/LLWU_P17_12") (pintype "bidirectional"))
    )
    (net (code "123") (name "unconnected-(IC1-PTE10{slash}LLWU_P18-Pad13)") (class "Default")
      (node (ref "IC1") (pin "13") (pinfunction "PTE10/LLWU_P18_13") (pintype "bidirectional"))
    )
    (net (code "124") (name "unconnected-(IC1-PTE11-Pad14)") (class "Default")
      (node (ref "IC1") (pin "14") (pinfunction "PTE11_14") (pintype "bidirectional"))
    )
    (net (code "125") (name "unconnected-(IC1-RTC_WAKEUP_B-Pad30)") (class "Default")
      (node (ref "IC1") (pin "30") (pinfunction "RTC_WAKEUP_B_30") (pintype "bidirectional"))
    )
    (net (code "126") (name "unconnected-(IC1-VBAT-Pad33)") (class "Default")
      (node (ref "IC1") (pin "33") (pinfunction "VBAT_33") (pintype "bidirectional"))
    )
    (net (code "127") (name "unconnected-(IC1-VOUT33-Pad19)") (class "Default")
      (node (ref "IC1") (pin "19") (pinfunction "VOUT33_19") (pintype "bidirectional"))
    )
    (net (code "128") (name "unconnected-(IC1-VREF_OUT{slash}CMP1_IN5{slash}CMP0_IN5{slash}ADC0_SE22-Pad28)") (class "Default")
      (node (ref "IC1") (pin "28") (pinfunction "VREF_OUT/CMP1_IN5/CMP0_IN5/ADC0_SE22_28") (pintype "bidirectional"))
    )
    (net (code "129") (name "unconnected-(IC1-VREGIN-Pad20)") (class "Default")
      (node (ref "IC1") (pin "20") (pinfunction "VREGIN_20") (pintype "bidirectional"))
    )
    (net (code "130") (name "unconnected-(IC1-XTAL32-Pad31)") (class "Default")
      (node (ref "IC1") (pin "31") (pinfunction "XTAL32_31") (pintype "bidirectional"))
    )
    (net (code "131") (name "unconnected-(IC3-IO_2{slash}MOSI{slash}CSI_B-Pad46)") (class "Default")
      (node (ref "IC3") (pin "46") (pinfunction "IO_2/MOSI/CSI_B_46") (pintype "bidirectional"))
    )
    (net (code "132") (name "unconnected-(IC3-IO_L01N_2{slash}M0-Pad25)") (class "Default")
      (node (ref "IC3") (pin "25") (pinfunction "IO_L01N_2/M0_25") (pintype "bidirectional"))
    )
    (net (code "133") (name "unconnected-(IC3-IO_L01N_3-Pad4)") (class "Default")
      (node (ref "IC3") (pin "4") (pinfunction "IO_L01N_3_4") (pintype "bidirectional"))
    )
    (net (code "134") (name "unconnected-(IC3-IO_L01P_2{slash}M1-Pad23)") (class "Default")
      (node (ref "IC3") (pin "23") (pinfunction "IO_L01P_2/M1_23") (pintype "bidirectional"))
    )
    (net (code "135") (name "unconnected-(IC3-IO_L01P_3-Pad3)") (class "Default")
      (node (ref "IC3") (pin "3") (pinfunction "IO_L01P_3_3") (pintype "bidirectional"))
    )
    (net (code "136") (name "unconnected-(IC3-IO_L02N_0{slash}GCLK5-Pad84)") (class "Default")
      (node (ref "IC3") (pin "84") (pinfunction "IO_L02N_0/GCLK5_84") (pintype "bidirectional"))
    )
    (net (code "137") (name "unconnected-(IC3-IO_L02N_2{slash}CSO_B-Pad27)") (class "Default")
      (node (ref "IC3") (pin "27") (pinfunction "IO_L02N_2/CSO_B_27") (pintype "bidirectional"))
    )
    (net (code "138") (name "unconnected-(IC3-IO_L02N_3-Pad6)") (class "Default")
      (node (ref "IC3") (pin "6") (pinfunction "IO_L02N_3_6") (pintype "bidirectional"))
    )
    (net (code "139") (name "unconnected-(IC3-IO_L02P_0{slash}GCLK4-Pad83)") (class "Default")
      (node (ref "IC3") (pin "83") (pinfunction "IO_L02P_0/GCLK4_83") (pintype "bidirectional"))
    )
    (net (code "140") (name "unconnected-(IC3-IO_L02P_2{slash}M2-Pad24)") (class "Default")
      (node (ref "IC3") (pin "24") (pinfunction "IO_L02P_2/M2_24") (pintype "bidirectional"))
    )
    (net (code "141") (name "unconnected-(IC3-IO_L02P_3-Pad5)") (class "Default")
      (node (ref "IC3") (pin "5") (pinfunction "IO_L02P_3_5") (pintype "bidirectional"))
    )
    (net (code "142") (name "unconnected-(IC3-IO_L03N_0{slash}GCLK7-Pad86)") (class "Default")
      (node (ref "IC3") (pin "86") (pinfunction "IO_L03N_0/GCLK7_86") (pintype "bidirectional"))
    )
    (net (code "143") (name "unconnected-(IC3-IO_L03N_1{slash}TRDY1{slash}RHCLK3-Pad62)") (class "Default")
      (node (ref "IC3") (pin "62") (pinfunction "IO_L03N_1/TRDY1/RHCLK3_62") (pintype "bidirectional"))
    )
    (net (code "144") (name "unconnected-(IC3-IO_L03N_2{slash}VS1-Pad30)") (class "Default")
      (node (ref "IC3") (pin "30") (pinfunction "IO_L03N_2/VS1_30") (pintype "bidirectional"))
    )
    (net (code "145") (name "unconnected-(IC3-IO_L03N_3{slash}LHCLK1-Pad10)") (class "Default")
      (node (ref "IC3") (pin "10") (pinfunction "IO_L03N_3/LHCLK1_10") (pintype "bidirectional"))
    )
    (net (code "146") (name "unconnected-(IC3-IO_L03P_0{slash}GCLK6-Pad85)") (class "Default")
      (node (ref "IC3") (pin "85") (pinfunction "IO_L03P_0/GCLK6_85") (pintype "bidirectional"))
    )
    (net (code "147") (name "unconnected-(IC3-IO_L03P_2{slash}RDWR_B-Pad28)") (class "Default")
      (node (ref "IC3") (pin "28") (pinfunction "IO_L03P_2/RDWR_B_28") (pintype "bidirectional"))
    )
    (net (code "148") (name "unconnected-(IC3-IO_L03P_3{slash}LHCLK0-Pad9)") (class "Default")
      (node (ref "IC3") (pin "9") (pinfunction "IO_L03P_3/LHCLK0_9") (pintype "bidirectional"))
    )
    (net (code "149") (name "unconnected-(IC3-IO_L04N_2{slash}VS0-Pad31)") (class "Default")
      (node (ref "IC3") (pin "31") (pinfunction "IO_L04N_2/VS0_31") (pintype "bidirectional"))
    )
    (net (code "150") (name "unconnected-(IC3-IO_L04N_3{slash}IRDY2{slash}LHCLK3-Pad13)") (class "Default")
      (node (ref "IC3") (pin "13") (pinfunction "IO_L04N_3/IRDY2/LHCLK3_13") (pintype "bidirectional"))
    )
    (net (code "151") (name "unconnected-(IC3-IO_L04P_2{slash}VS2-Pad29)") (class "Default")
      (node (ref "IC3") (pin "29") (pinfunction "IO_L04P_2/VS2_29") (pintype "bidirectional"))
    )
    (net (code "152") (name "unconnected-(IC3-IO_L04P_3{slash}LHCLK2-Pad12)") (class "Default")
      (node (ref "IC3") (pin "12") (pinfunction "IO_L04P_3/LHCLK2_12") (pintype "bidirectional"))
    )
    (net (code "153") (name "unconnected-(IC3-IO_L05N_0-Pad94)") (class "Default")
      (node (ref "IC3") (pin "94") (pinfunction "IO_L05N_0_94") (pintype "bidirectional"))
    )
    (net (code "154") (name "unconnected-(IC3-IO_L05N_2{slash}D7-Pad34)") (class "Default")
      (node (ref "IC3") (pin "34") (pinfunction "IO_L05N_2/D7_34") (pintype "bidirectional"))
    )
    (net (code "155") (name "unconnected-(IC3-IO_L05N_3{slash}LHCLK7-Pad16)") (class "Default")
      (node (ref "IC3") (pin "16") (pinfunction "IO_L05N_3/LHCLK7_16") (pintype "bidirectional"))
    )
    (net (code "156") (name "unconnected-(IC3-IO_L05P_2-Pad32)") (class "Default")
      (node (ref "IC3") (pin "32") (pinfunction "IO_L05P_2_32") (pintype "bidirectional"))
    )
    (net (code "157") (name "unconnected-(IC3-IO_L05P_3{slash}TRDY2{slash}LHCLK6-Pad15)") (class "Default")
      (node (ref "IC3") (pin "15") (pinfunction "IO_L05P_3/TRDY2/LHCLK6_15") (pintype "bidirectional"))
    )
    (net (code "158") (name "unconnected-(IC3-IO_L06N_0{slash}PUDC_B-Pad99)") (class "Default")
      (node (ref "IC3") (pin "99") (pinfunction "IO_L06N_0/PUDC_B_99") (pintype "bidirectional"))
    )
    (net (code "159") (name "unconnected-(IC3-IO_L06N_2{slash}D6-Pad35)") (class "Default")
      (node (ref "IC3") (pin "35") (pinfunction "IO_L06N_2/D6_35") (pintype "bidirectional"))
    )
    (net (code "160") (name "unconnected-(IC3-IO_L06N_3-Pad20)") (class "Default")
      (node (ref "IC3") (pin "20") (pinfunction "IO_L06N_3_20") (pintype "bidirectional"))
    )
    (net (code "161") (name "unconnected-(IC3-IO_L06P_0{slash}VREF_0-Pad98)") (class "Default")
      (node (ref "IC3") (pin "98") (pinfunction "IO_L06P_0/VREF_0_98") (pintype "bidirectional"))
    )
    (net (code "162") (name "unconnected-(IC3-IO_L06P_2-Pad33)") (class "Default")
      (node (ref "IC3") (pin "33") (pinfunction "IO_L06P_2_33") (pintype "bidirectional"))
    )
    (net (code "163") (name "unconnected-(IC3-IO_L06P_3-Pad19)") (class "Default")
      (node (ref "IC3") (pin "19") (pinfunction "IO_L06P_3_19") (pintype "bidirectional"))
    )
    (net (code "164") (name "unconnected-(IC3-IO_L09N_2{slash}GCLK1-Pad44)") (class "Default")
      (node (ref "IC3") (pin "44") (pinfunction "IO_L09N_2/GCLK1_44") (pintype "bidirectional"))
    )
    (net (code "165") (name "unconnected-(IC3-IO_L09P_2{slash}GCLK0-Pad43)") (class "Default")
      (node (ref "IC3") (pin "43") (pinfunction "IO_L09P_2/GCLK0_43") (pintype "bidirectional"))
    )
    (net (code "166") (name "unconnected-(IC3-IP_0-Pad97)") (class "Default")
      (node (ref "IC3") (pin "97") (pinfunction "IP_0_97") (pintype "bidirectional"))
    )
    (net (code "167") (name "unconnected-(IC3-IP_0{slash}VREF_0-Pad82)") (class "Default")
      (node (ref "IC3") (pin "82") (pinfunction "IP_0/VREF_0_82") (pintype "bidirectional"))
    )
    (net (code "168") (name "unconnected-(IC3-IP_1{slash}VREF_1-Pad68)") (class "Default")
      (node (ref "IC3") (pin "68") (pinfunction "IP_1/VREF_1_68") (pintype "bidirectional"))
    )
    (net (code "169") (name "unconnected-(IC3-IP_2{slash}VREF_2-Pad39)") (class "Default")
      (node (ref "IC3") (pin "39") (pinfunction "IP_2/VREF_2_39") (pintype "bidirectional"))
    )
    (net (code "170") (name "unconnected-(IC3-IP_3-Pad21)") (class "Default")
      (node (ref "IC3") (pin "21") (pinfunction "IP_3_21") (pintype "bidirectional"))
    )
    (net (code "171") (name "unconnected-(IC3-IP_3{slash}VREF_3-Pad7)") (class "Default")
      (node (ref "IC3") (pin "7") (pinfunction "IP_3/VREF_3_7") (pintype "bidirectional"))
    )
    (net (code "172") (name "unconnected-(IC3-TCK-Pad76)") (class "Default")
      (node (ref "IC3") (pin "76") (pinfunction "TCK_76") (pintype "bidirectional"))
    )
    (net (code "173") (name "unconnected-(IC3-TDI-Pad2)") (class "Default")
      (node (ref "IC3") (pin "2") (pinfunction "TDI_2") (pintype "bidirectional"))
    )
    (net (code "174") (name "unconnected-(IC3-TDO-Pad75)") (class "Default")
      (node (ref "IC3") (pin "75") (pinfunction "TDO_75") (pintype "bidirectional"))
    )
    (net (code "175") (name "unconnected-(IC3-TMS-Pad1)") (class "Default")
      (node (ref "IC3") (pin "1") (pinfunction "TMS_1") (pintype "bidirectional"))
    )
    (net (code "176") (name "unconnected-(IC4-~{OC}-Pad8)") (class "Default")
      (node (ref "IC4") (pin "8") (pinfunction "~{OC}_8") (pintype "bidirectional"))
    )
    (net (code "177") (name "unconnected-(J1-ID-Pad4)") (class "Default")
      (node (ref "J1") (pin "4") (pinfunction "ID_4") (pintype "bidirectional"))
    )
    (net (code "178") (name "unconnected-(J2-CARD_DETECTION_SWITCH_(A)-Pad9)") (class "Default")
      (node (ref "J2") (pin "9") (pinfunction "CARD_DETECTION_SWITCH_(A)_9") (pintype "bidirectional"))
    )
    (net (code "179") (name "unconnected-(J2-CARD_DETECTION_SWITCH_(B)-Pad10)") (class "Default")
      (node (ref "J2") (pin "10") (pinfunction "CARD_DETECTION_SWITCH_(B)_10") (pintype "bidirectional"))
    )
    (net (code "180") (name "unconnected-(J2-DAT1-Pad8)") (class "Default")
      (node (ref "J2") (pin "8") (pinfunction "DAT1_8") (pintype "bidirectional"))
    )
    (net (code "181") (name "unconnected-(J2-DAT2-Pad1)") (class "Default")
      (node (ref "J2") (pin "1") (pinfunction "DAT2_1") (pintype "bidirectional"))
    )
  )
)
